# Memory.net
KiCad netlist of a schematic drawn in EAGLE
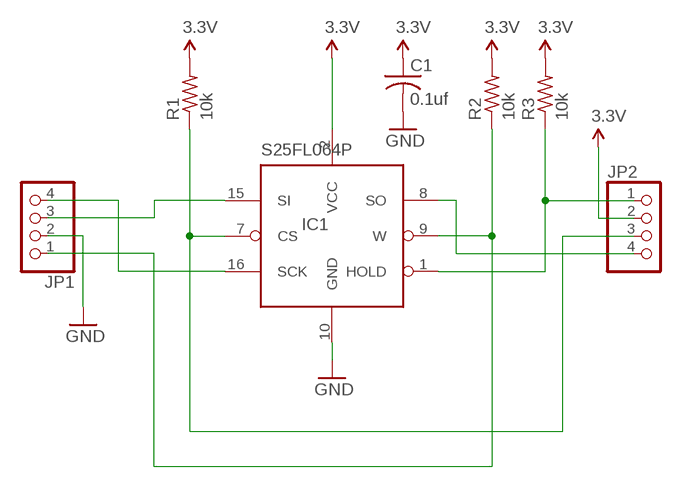
[diagram p0: schematic, sheet 1]

(export (version "E")
  (design (tool "Eeschema 10.0.6"))
  (components
    (comp (ref "C1")
      (value "0.1uf")
      (footprint "eagle-import:0603_CAP")
      (libsource (lib "eagle-import") (part "CAP0603"))
    )
    (comp (ref "IC1")
      (value "S25FL064P")
      (footprint "eagle-import:SOIC-16")
      (libsource (lib "eagle-import") (part "S25FL064P"))
    )
    (comp (ref "JP1")
      (value "PINHD-1X4")
      (footprint "eagle-import:1X04")
      (libsource (lib "eagle-import") (part "PINHD-1X4"))
    )
    (comp (ref "JP2")
      (value "PINHD-1X4")
      (footprint "eagle-import:1X04")
      (libsource (lib "eagle-import") (part "PINHD-1X4"))
    )
    (comp (ref "R1")
      (value "10k")
      (footprint "eagle-import:0603_RESISTOR")
      (libsource (lib "eagle-import") (part "RESISTOR0603"))
    )
    (comp (ref "R2")
      (value "10k")
      (footprint "eagle-import:0603_RESISTOR")
      (libsource (lib "eagle-import") (part "RESISTOR0603"))
    )
    (comp (ref "R3")
      (value "10k")
      (footprint "eagle-import:0603_RESISTOR")
      (libsource (lib "eagle-import") (part "RESISTOR0603"))
    )
  )
  (nets
    (net (code "1") (name "3.3V") (class "Default")
      (node (ref "C1") (pin "1") (pinfunction "1_1") (pintype "passive"))
      (node (ref "IC1") (pin "2") (pinfunction "VCC_2") (pintype "power_in"))
      (node (ref "JP2") (pin "2") (pinfunction "2_2") (pintype "passive"))
      (node (ref "R1") (pin "2") (pinfunction "2_2") (pintype "passive"))
      (node (ref "R2") (pin "2") (pinfunction "2_2") (pintype "passive"))
      (node (ref "R3") (pin "2") (pinfunction "2_2") (pintype "passive"))
    )
    (net (code "2") (name "GND") (class "Default")
      (node (ref "C1") (pin "2") (pinfunction "2_2") (pintype "passive"))
      (node (ref "IC1") (pin "10") (pinfunction "GND_10") (pintype "power_in"))
      (node (ref "JP1") (pin "2") (pinfunction "2_2") (pintype "passive"))
    )
    (net (code "3") (name "Net-(IC1-CS)") (class "Default")
      (node (ref "IC1") (pin "7") (pinfunction "CS_7") (pintype "input"))
      (node (ref "JP2") (pin "3") (pinfunction "3_3") (pintype "passive"))
      (node (ref "R1") (pin "1") (pinfunction "1_1") (pintype "passive"))
    )
    (net (code "4") (name "Net-(IC1-HOLD)") (class "Default")
      (node (ref "IC1") (pin "1") (pinfunction "HOLD_1") (pintype "input"))
      (node (ref "JP2") (pin "1") (pinfunction "1_1") (pintype "passive"))
      (node (ref "R3") (pin "1") (pinfunction "1_1") (pintype "passive"))
    )
    (net (code "5") (name "Net-(IC1-SCK)") (class "Default")
      (node (ref "IC1") (pin "16") (pinfunction "SCK_16") (pintype "input"))
      (node (ref "JP1") (pin "4") (pinfunction "4_4") (pintype "passive"))
    )
    (net (code "6") (name "Net-(IC1-SI)") (class "Default")
      (node (ref "IC1") (pin "15") (pinfunction "SI_15") (pintype "input"))
      (node (ref "JP1") (pin "3") (pinfunction "3_3") (pintype "passive"))
    )
    (net (code "7") (name "Net-(IC1-SO)") (class "Default")
      (node (ref "IC1") (pin "8") (pinfunction "SO_8") (pintype "output"))
      (node (ref "JP2") (pin "4") (pinfunction "4_4") (pintype "passive"))
    )
    (net (code "8") (name "Net-(IC1-W)") (class "Default")
      (node (ref "IC1") (pin "9") (pinfunction "W_9") (pintype "input"))
      (node (ref "JP1") (pin "1") (pinfunction "1_1") (pintype "passive"))
      (node (ref "R2") (pin "1") (pinfunction "1_1") (pintype "passive"))
    )
  )
)
